# USB-JTAG-Programmer_v4_0_1.net
KiCad netlist of a schematic drawn in EAGLE
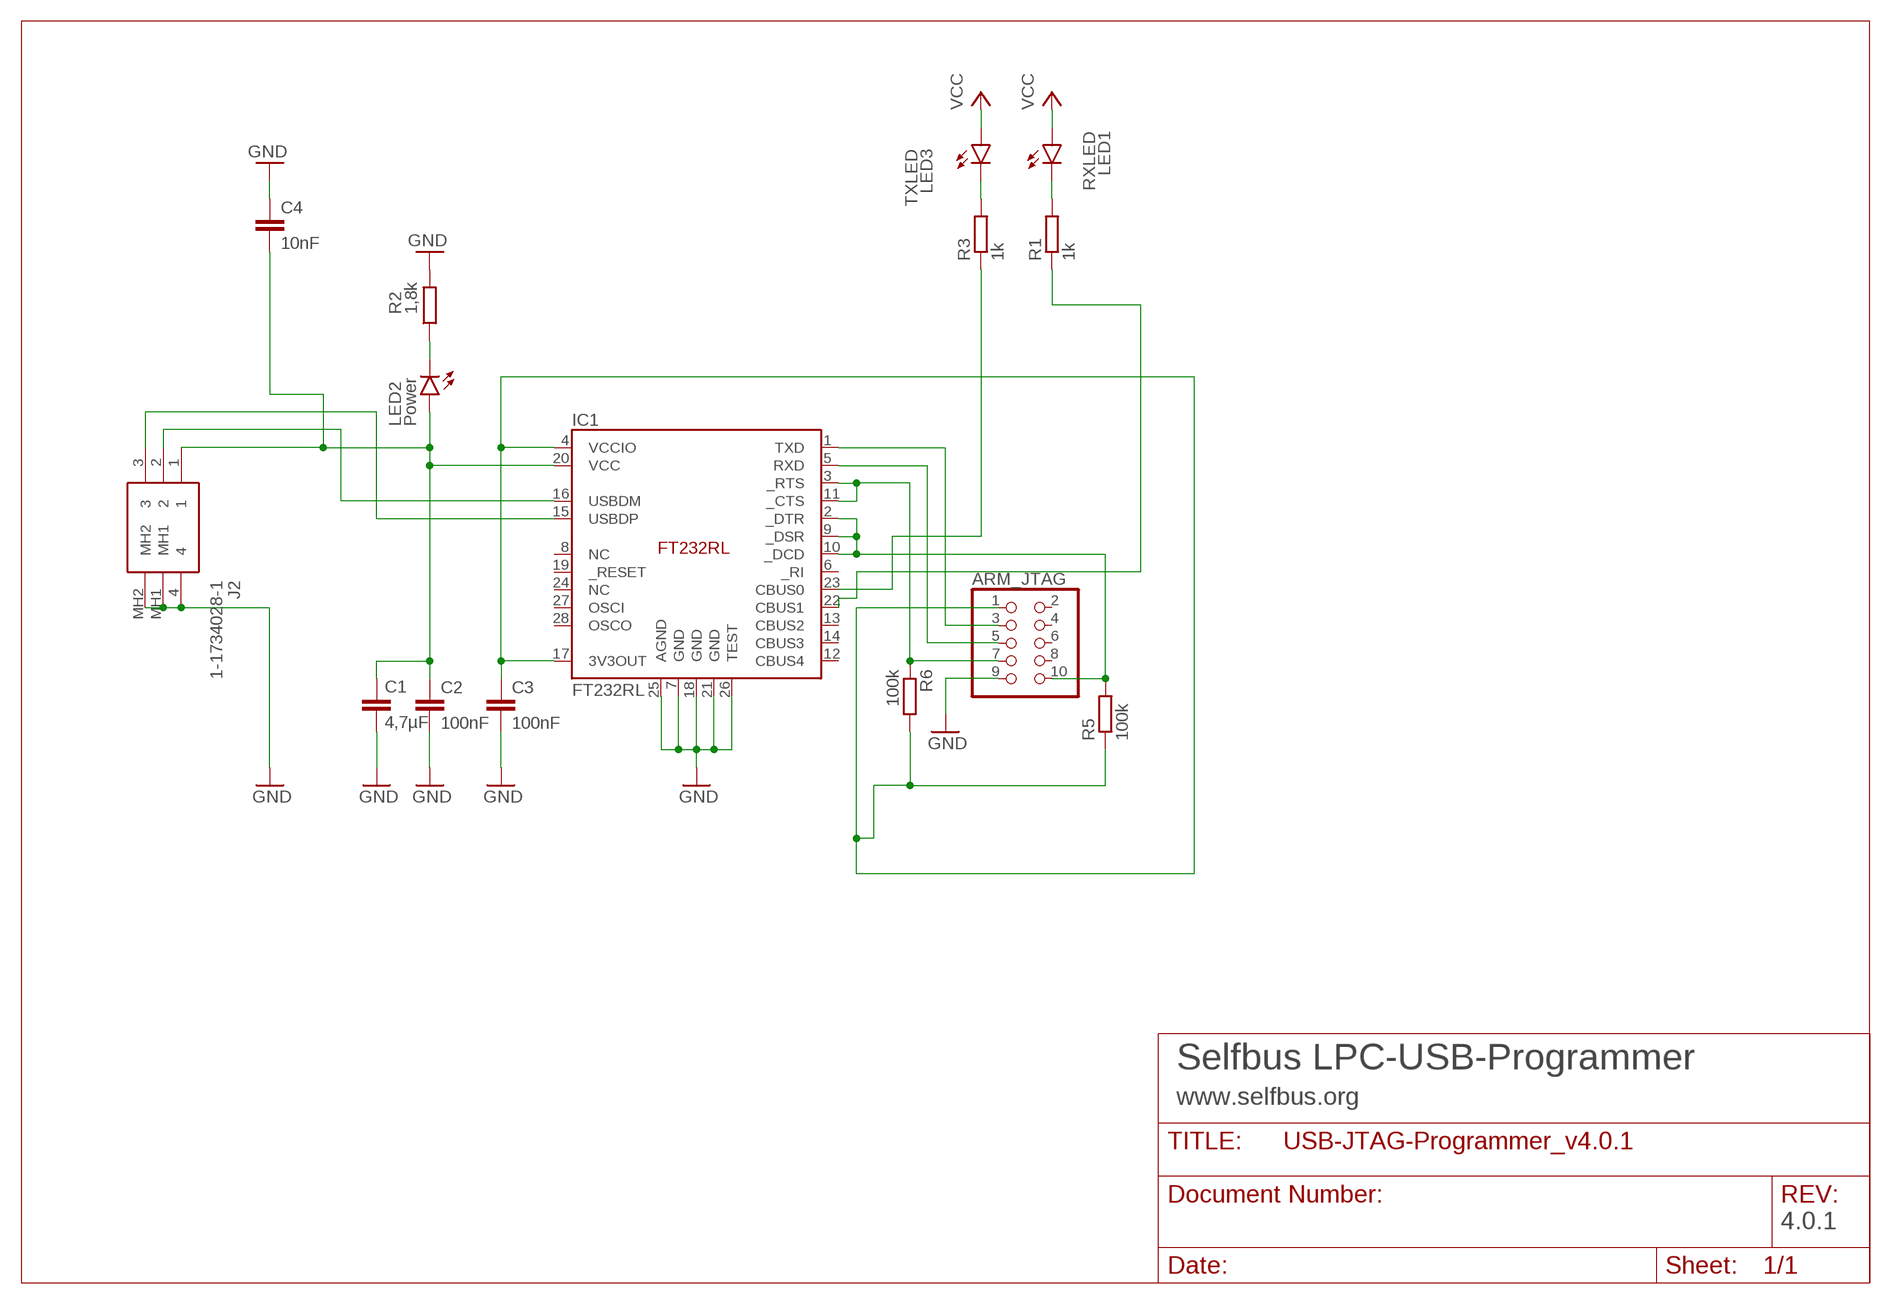
[diagram p0: schematic, sheet 1]

(export (version "E")
  (design (tool "Eeschema 10.0.6"))
  (components
    (comp (ref "ARM_JTAG")
      (value "PINHD-2X5_2.00")
      (footprint "eagle-import:2X05M")
      (libsource (lib "eagle-import") (part "PINHD-2X5_2.00"))
    )
    (comp (ref "C1")
      (value "4,7µF")
      (footprint "eagle-import:C1206K")
      (libsource (lib "eagle-import") (part "C-EUC1206K"))
    )
    (comp (ref "C2")
      (value "100nF")
      (footprint "eagle-import:C0805K")
      (libsource (lib "eagle-import") (part "C-EUC0805K"))
    )
    (comp (ref "C3")
      (value "100nF")
      (footprint "eagle-import:C0805K")
      (libsource (lib "eagle-import") (part "C-EUC0805K"))
    )
    (comp (ref "C4")
      (value "10nF")
      (footprint "eagle-import:C0805K")
      (libsource (lib "eagle-import") (part "C-EUC0805K"))
    )
    (comp (ref "IC1")
      (value "FT232RL")
      (footprint "eagle-import:SSOP-28")
      (libsource (lib "eagle-import") (part "FT232RL"))
    )
    (comp (ref "J2")
      (value "1-1734028-1")
      (footprint "eagle-import:117340281")
      (fields (field (name "MOUSER_PART_NUMBER") "571-1-1734028-1"))
      (libsource (lib "eagle-import") (part "1-1734028-1"))
    )
    (comp (ref "LED1")
      (value "RXLED")
      (footprint "eagle-import:CHIPLED_0805")
      (libsource (lib "eagle-import") (part "LEDCHIPLED_0805"))
    )
    (comp (ref "LED2")
      (value "Power")
      (footprint "eagle-import:CHIPLED_0805")
      (libsource (lib "eagle-import") (part "LEDCHIPLED_0805"))
    )
    (comp (ref "LED3")
      (value "TXLED")
      (footprint "eagle-import:CHIPLED_0805")
      (libsource (lib "eagle-import") (part "LEDCHIPLED_0805"))
    )
    (comp (ref "R1")
      (value "1k")
      (footprint "eagle-import:R0805")
      (libsource (lib "eagle-import") (part "resistor_348_R-EU_R0805"))
    )
    (comp (ref "R2")
      (value "1,8k")
      (footprint "eagle-import:R0805")
      (libsource (lib "eagle-import") (part "R-EU_R0805"))
    )
    (comp (ref "R3")
      (value "1k")
      (footprint "eagle-import:R0805")
      (libsource (lib "eagle-import") (part "resistor_348_R-EU_R0805"))
    )
    (comp (ref "R5")
      (value "100k")
      (footprint "eagle-import:R0805")
      (libsource (lib "eagle-import") (part "resistor_348_R-EU_R0805"))
    )
    (comp (ref "R6")
      (value "100k")
      (footprint "eagle-import:R0805")
      (libsource (lib "eagle-import") (part "R-EU_R0805"))
    )
  )
  (nets
    (net (code "1") (name "GND") (class "Default")
      (node (ref "ARM_JTAG") (pin "9") (pinfunction "9_9") (pintype "passive"))
      (node (ref "C1") (pin "2") (pinfunction "2_2") (pintype "passive"))
      (node (ref "C2") (pin "2") (pinfunction "2_2") (pintype "passive"))
      (node (ref "C3") (pin "2") (pinfunction "2_2") (pintype "passive"))
      (node (ref "C4") (pin "1") (pinfunction "1_1") (pintype "passive"))
      (node (ref "IC1") (pin "18") (pinfunction "GND_18") (pintype "power_in"))
      (node (ref "IC1") (pin "21") (pinfunction "GND_21") (pintype "power_in"))
      (node (ref "IC1") (pin "25") (pinfunction "AGND_25") (pintype "power_in"))
      (node (ref "IC1") (pin "26") (pinfunction "TEST_26") (pintype "bidirectional"))
      (node (ref "IC1") (pin "7") (pinfunction "GND_7") (pintype "power_in"))
      (node (ref "J2") (pin "4") (pinfunction "4_4") (pintype "bidirectional"))
      (node (ref "J2") (pin "MH1") (pinfunction "MH1_MH1") (pintype "bidirectional"))
      (node (ref "J2") (pin "MH2") (pinfunction "MH2_MH2") (pintype "bidirectional"))
      (node (ref "R2") (pin "2") (pinfunction "2_2") (pintype "passive"))
    )
    (net (code "2") (name "Net-(IC1-3V3OUT)") (class "Default")
      (node (ref "ARM_JTAG") (pin "1") (pinfunction "1_1") (pintype "passive"))
      (node (ref "C3") (pin "1") (pinfunction "1_1") (pintype "passive"))
      (node (ref "IC1") (pin "17") (pinfunction "3V3OUT_17") (pintype "output"))
      (node (ref "IC1") (pin "4") (pinfunction "VCCIO_4") (pintype "power_in"))
      (node (ref "R5") (pin "1") (pinfunction "1_1") (pintype "passive"))
      (node (ref "R6") (pin "2") (pinfunction "2_2") (pintype "passive"))
    )
    (net (code "3") (name "Net-(IC1-CBUS0)") (class "Default")
      (node (ref "IC1") (pin "23") (pinfunction "CBUS0_23") (pintype "bidirectional"))
      (node (ref "R3") (pin "1") (pinfunction "1_1") (pintype "passive"))
    )
    (net (code "4") (name "Net-(IC1-CBUS1)") (class "Default")
      (node (ref "IC1") (pin "22") (pinfunction "CBUS1_22") (pintype "bidirectional"))
      (node (ref "R1") (pin "1") (pinfunction "1_1") (pintype "passive"))
    )
    (net (code "5") (name "Net-(IC1-RXD)") (class "Default")
      (node (ref "ARM_JTAG") (pin "5") (pinfunction "5_5") (pintype "passive"))
      (node (ref "IC1") (pin "5") (pinfunction "RXD_5") (pintype "input"))
    )
    (net (code "6") (name "Net-(IC1-TXD)") (class "Default")
      (node (ref "ARM_JTAG") (pin "3") (pinfunction "3_3") (pintype "passive"))
      (node (ref "IC1") (pin "1") (pinfunction "TXD_1") (pintype "output"))
    )
    (net (code "7") (name "Net-(IC1-USBDM)") (class "Default")
      (node (ref "IC1") (pin "16") (pinfunction "USBDM_16") (pintype "bidirectional"))
      (node (ref "J2") (pin "2") (pinfunction "2_2") (pintype "bidirectional"))
    )
    (net (code "8") (name "Net-(IC1-USBDP)") (class "Default")
      (node (ref "IC1") (pin "15") (pinfunction "USBDP_15") (pintype "bidirectional"))
      (node (ref "J2") (pin "3") (pinfunction "3_3") (pintype "bidirectional"))
    )
    (net (code "9") (name "Net-(IC1-_CTS)") (class "Default")
      (node (ref "ARM_JTAG") (pin "7") (pinfunction "7_7") (pintype "passive"))
      (node (ref "IC1") (pin "11") (pinfunction "_CTS_11") (pintype "input"))
      (node (ref "IC1") (pin "3") (pinfunction "_RTS_3") (pintype "output"))
      (node (ref "R6") (pin "1") (pinfunction "1_1") (pintype "passive"))
    )
    (net (code "10") (name "Net-(IC1-_DCD)") (class "Default")
      (node (ref "ARM_JTAG") (pin "10") (pinfunction "10_10") (pintype "passive"))
      (node (ref "IC1") (pin "10") (pinfunction "_DCD_10") (pintype "input"))
      (node (ref "IC1") (pin "2") (pinfunction "_DTR_2") (pintype "input"))
      (node (ref "IC1") (pin "9") (pinfunction "_DSR_9") (pintype "input"))
      (node (ref "R5") (pin "2") (pinfunction "2_2") (pintype "passive"))
    )
    (net (code "11") (name "Net-(LED1-PadC)") (class "Default")
      (node (ref "LED1") (pin "C") (pinfunction "C_C") (pintype "passive"))
      (node (ref "R1") (pin "2") (pinfunction "2_2") (pintype "passive"))
    )
    (net (code "12") (name "Net-(LED2-PadC)") (class "Default")
      (node (ref "LED2") (pin "C") (pinfunction "C_C") (pintype "passive"))
      (node (ref "R2") (pin "1") (pinfunction "1_1") (pintype "passive"))
    )
    (net (code "13") (name "Net-(LED3-PadC)") (class "Default")
      (node (ref "LED3") (pin "C") (pinfunction "C_C") (pintype "passive"))
      (node (ref "R3") (pin "2") (pinfunction "2_2") (pintype "passive"))
    )
    (net (code "14") (name "VCC") (class "Default")
      (node (ref "C1") (pin "1") (pinfunction "1_1") (pintype "passive"))
      (node (ref "C2") (pin "1") (pinfunction "1_1") (pintype "passive"))
      (node (ref "C4") (pin "2") (pinfunction "2_2") (pintype "passive"))
      (node (ref "IC1") (pin "20") (pinfunction "VCC_20") (pintype "power_in"))
      (node (ref "J2") (pin "1") (pinfunction "1_1") (pintype "bidirectional"))
      (node (ref "LED1") (pin "A") (pinfunction "A_A") (pintype "passive"))
      (node (ref "LED2") (pin "A") (pinfunction "A_A") (pintype "passive"))
      (node (ref "LED3") (pin "A") (pinfunction "A_A") (pintype "passive"))
    )
    (net (code "15") (name "unconnected-(ARM_JTAG-Pad2)") (class "Default")
      (node (ref "ARM_JTAG") (pin "2") (pinfunction "2_2") (pintype "passive"))
    )
    (net (code "16") (name "unconnected-(ARM_JTAG-Pad4)") (class "Default")
      (node (ref "ARM_JTAG") (pin "4") (pinfunction "4_4") (pintype "passive"))
    )
    (net (code "17") (name "unconnected-(ARM_JTAG-Pad6)") (class "Default")
      (node (ref "ARM_JTAG") (pin "6") (pinfunction "6_6") (pintype "passive"))
    )
    (net (code "18") (name "unconnected-(ARM_JTAG-Pad8)") (class "Default")
      (node (ref "ARM_JTAG") (pin "8") (pinfunction "8_8") (pintype "passive"))
    )
    (net (code "19") (name "unconnected-(IC1-CBUS2-Pad13)") (class "Default")
      (node (ref "IC1") (pin "13") (pinfunction "CBUS2_13") (pintype "bidirectional"))
    )
    (net (code "20") (name "unconnected-(IC1-CBUS3-Pad14)") (class "Default")
      (node (ref "IC1") (pin "14") (pinfunction "CBUS3_14") (pintype "bidirectional"))
    )
    (net (code "21") (name "unconnected-(IC1-CBUS4-Pad12)") (class "Default")
      (node (ref "IC1") (pin "12") (pinfunction "CBUS4_12") (pintype "bidirectional"))
    )
    (net (code "22") (name "unconnected-(IC1-NC-Pad8)") (class "Default")
      (node (ref "IC1") (pin "8") (pinfunction "NC_8") (pintype "no_connect"))
    )
    (net (code "23") (name "unconnected-(IC1-NC-Pad24)") (class "Default")
      (node (ref "IC1") (pin "24") (pinfunction "NC_24") (pintype "no_connect"))
    )
    (net (code "24") (name "unconnected-(IC1-OSCI-Pad27)") (class "Default")
      (node (ref "IC1") (pin "27") (pinfunction "OSCI_27") (pintype "input"))
    )
    (net (code "25") (name "unconnected-(IC1-OSCO-Pad28)") (class "Default")
      (node (ref "IC1") (pin "28") (pinfunction "OSCO_28") (pintype "output"))
    )
    (net (code "26") (name "unconnected-(IC1-_RESET-Pad19)") (class "Default")
      (node (ref "IC1") (pin "19") (pinfunction "_RESET_19") (pintype "input"))
    )
    (net (code "27") (name "unconnected-(IC1-_RI-Pad6)") (class "Default")
      (node (ref "IC1") (pin "6") (pinfunction "_RI_6") (pintype "input"))
    )
  )
)
